# v2.net
KiCad netlist of a schematic drawn in Altium Designer
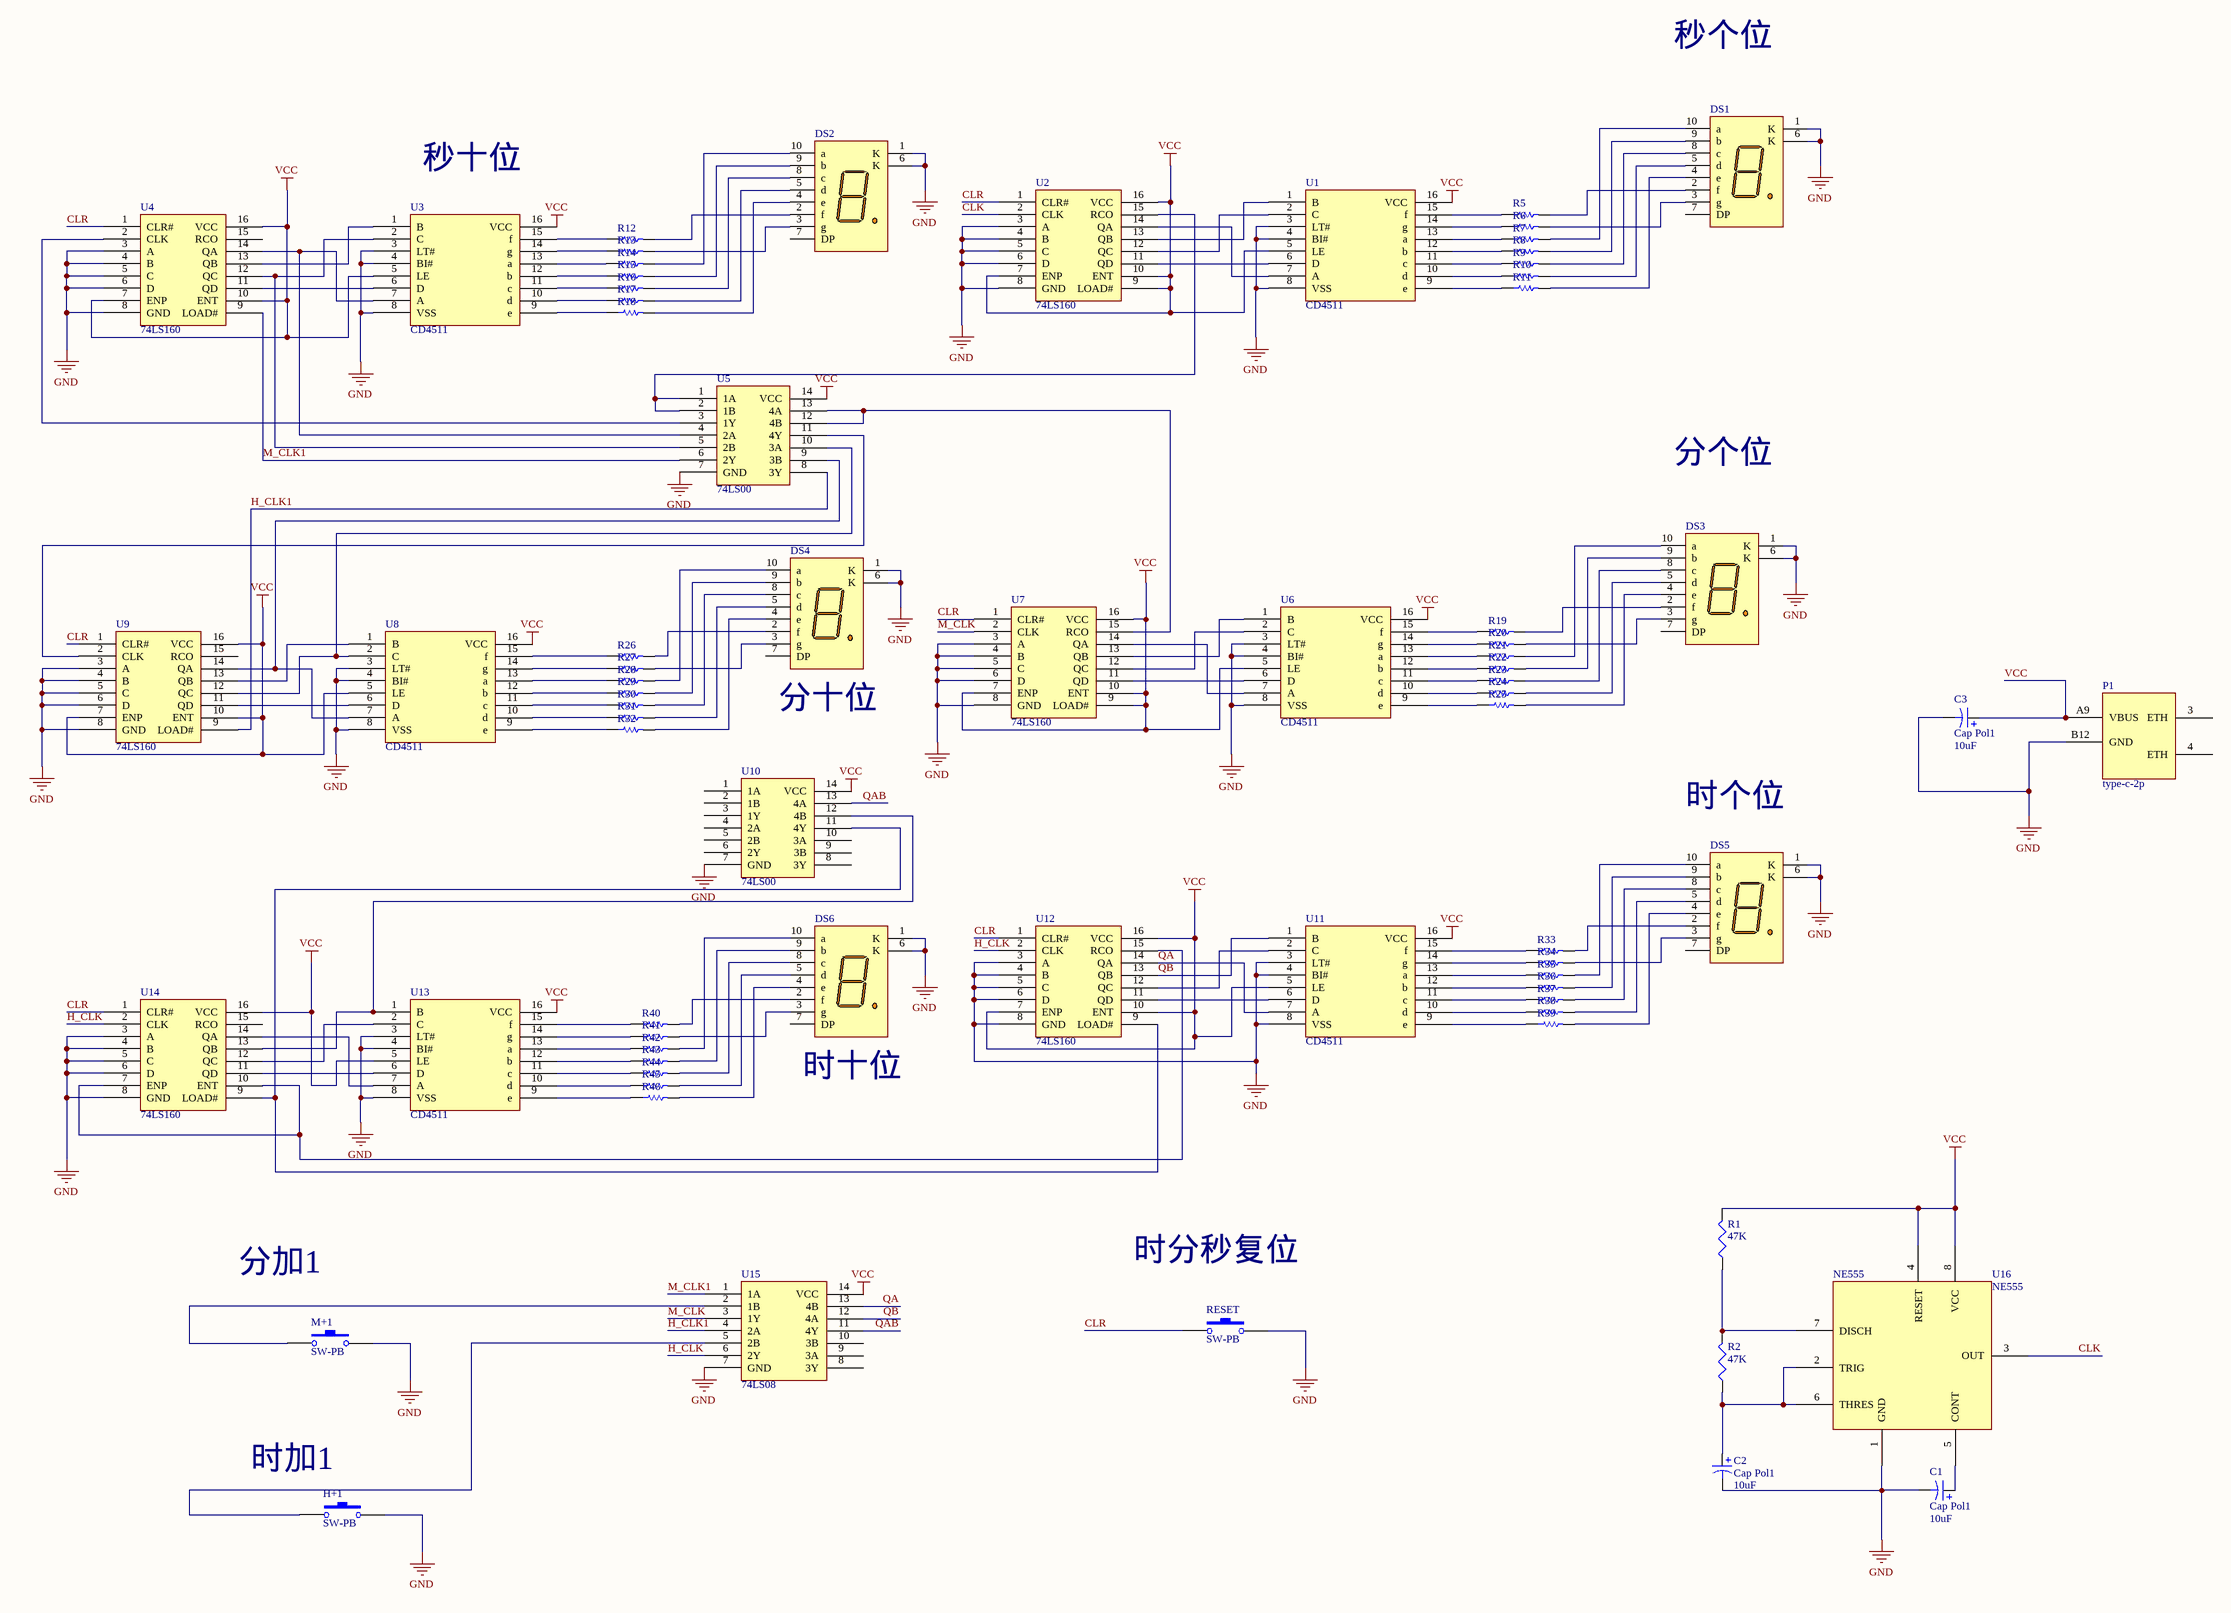
[diagram p0: 数字时钟v2.SchDoc]

(export (version "E")
  (design (tool "Eeschema 10.0.6"))
  (components
    (comp (ref "C1")
      (value "Cap Pol1")
      (footprint "RB7.6-15")
      (description "Polarized Capacitor (Radial)")
      (fields (field (name "ALTIUM_VALUE") "10uF") (field (name "PUBLISHER") "Altium Limited"))
      (libsource (lib "Miscellaneous Devices") (part "Cap Pol1"))
    )
    (comp (ref "C2")
      (value "Cap Pol1")
      (footprint "RB7.6-15")
      (description "Polarized Capacitor (Radial)")
      (fields (field (name "ALTIUM_VALUE") "10uF") (field (name "PUBLISHER") "Altium Limited"))
      (libsource (lib "Miscellaneous Devices") (part "Cap Pol1"))
    )
    (comp (ref "C3")
      (value "Cap Pol1")
      (footprint "RB7.6-15")
      (description "Polarized Capacitor (Radial)")
      (fields (field (name "ALTIUM_VALUE") "10uF") (field (name "PUBLISHER") "Altium Limited"))
      (libsource (lib "Miscellaneous Devices") (part "Cap Pol1"))
    )
    (comp (ref "DS1")
      (value "Dpy Amber-CC")
      (footprint "A")
      (description "7.62 mm Black Surface Orange 7-Segment Display: CC, RH DP")
      (fields (field (name "PUBLISHER") "Altium Limited"))
      (libsource (lib "Miscellaneous Devices") (part "Dpy Amber-CC"))
    )
    (comp (ref "DS2")
      (value "Dpy Amber-CC")
      (footprint "A")
      (description "7.62 mm Black Surface Orange 7-Segment Display: CC, RH DP")
      (fields (field (name "PUBLISHER") "Altium Limited"))
      (libsource (lib "Miscellaneous Devices") (part "Dpy Amber-CC"))
    )
    (comp (ref "DS3")
      (value "Dpy Amber-CC")
      (footprint "A")
      (description "7.62 mm Black Surface Orange 7-Segment Display: CC, RH DP")
      (fields (field (name "PUBLISHER") "Altium Limited"))
      (libsource (lib "Miscellaneous Devices") (part "Dpy Amber-CC"))
    )
    (comp (ref "DS4")
      (value "Dpy Amber-CC")
      (footprint "A")
      (description "7.62 mm Black Surface Orange 7-Segment Display: CC, RH DP")
      (fields (field (name "PUBLISHER") "Altium Limited"))
      (libsource (lib "Miscellaneous Devices") (part "Dpy Amber-CC"))
    )
    (comp (ref "DS5")
      (value "Dpy Amber-CC")
      (footprint "A")
      (description "7.62 mm Black Surface Orange 7-Segment Display: CC, RH DP")
      (fields (field (name "PUBLISHER") "Altium Limited"))
      (libsource (lib "Miscellaneous Devices") (part "Dpy Amber-CC"))
    )
    (comp (ref "DS6")
      (value "Dpy Amber-CC")
      (footprint "A")
      (description "7.62 mm Black Surface Orange 7-Segment Display: CC, RH DP")
      (fields (field (name "PUBLISHER") "Altium Limited"))
      (libsource (lib "Miscellaneous Devices") (part "Dpy Amber-CC"))
    )
    (comp (ref "H+1")
      (value "SW-PB")
      (footprint "按键")
      (description "Switch")
      (fields (field (name "PUBLISHER") "Altium Limited"))
      (libsource (lib "Miscellaneous Devices") (part "SW-PB"))
    )
    (comp (ref "M+1")
      (value "SW-PB")
      (footprint "按键")
      (description "Switch")
      (fields (field (name "PUBLISHER") "Altium Limited"))
      (libsource (lib "Miscellaneous Devices") (part "SW-PB"))
    )
    (comp (ref "P1")
      (value "type-c-2p")
      (footprint "type-c-2p")
      (libsource (lib "数字电路时钟") (part "type-c-2p"))
    )
    (comp (ref "R1")
      (value "47K")
      (footprint "AXIAL-0.3")
      (description "Resistor")
      (fields (field (name "Comment") "Res3") (field (name "PUBLISHER") "Altium Limited"))
      (libsource (lib "Miscellaneous Devices") (part "Res3"))
    )
    (comp (ref "R2")
      (value "47K")
      (footprint "AXIAL-0.3")
      (description "Resistor")
      (fields (field (name "Comment") "Res3") (field (name "PUBLISHER") "Altium Limited"))
      (libsource (lib "Miscellaneous Devices") (part "Res3"))
    )
    (comp (ref "R5")
      (value "Res1")
      (footprint "AXIAL-0.3")
      (description "Resistor")
      (fields (field (name "PUBLISHER") "Altium Limited"))
      (libsource (lib "Miscellaneous Devices") (part "Res1"))
    )
    (comp (ref "R6")
      (value "Res1")
      (footprint "AXIAL-0.3")
      (description "Resistor")
      (fields (field (name "PUBLISHER") "Altium Limited"))
      (libsource (lib "Miscellaneous Devices") (part "Res1"))
    )
    (comp (ref "R7")
      (value "Res1")
      (footprint "AXIAL-0.3")
      (description "Resistor")
      (fields (field (name "PUBLISHER") "Altium Limited"))
      (libsource (lib "Miscellaneous Devices") (part "Res1"))
    )
    (comp (ref "R8")
      (value "Res1")
      (footprint "AXIAL-0.3")
      (description "Resistor")
      (fields (field (name "PUBLISHER") "Altium Limited"))
      (libsource (lib "Miscellaneous Devices") (part "Res1"))
    )
    (comp (ref "R9")
      (value "Res1")
      (footprint "AXIAL-0.3")
      (description "Resistor")
      (fields (field (name "PUBLISHER") "Altium Limited"))
      (libsource (lib "Miscellaneous Devices") (part "Res1"))
    )
    (comp (ref "R10")
      (value "Res1")
      (footprint "AXIAL-0.3")
      (description "Resistor")
      (fields (field (name "PUBLISHER") "Altium Limited"))
      (libsource (lib "Miscellaneous Devices") (part "Res1"))
    )
    (comp (ref "R11")
      (value "Res1")
      (footprint "AXIAL-0.3")
      (description "Resistor")
      (fields (field (name "PUBLISHER") "Altium Limited"))
      (libsource (lib "Miscellaneous Devices") (part "Res1"))
    )
    (comp (ref "R12")
      (value "Res1")
      (footprint "AXIAL-0.3")
      (description "Resistor")
      (fields (field (name "PUBLISHER") "Altium Limited"))
      (libsource (lib "Miscellaneous Devices") (part "Res1"))
    )
    (comp (ref "R13")
      (value "Res1")
      (footprint "AXIAL-0.3")
      (description "Resistor")
      (fields (field (name "PUBLISHER") "Altium Limited"))
      (libsource (lib "Miscellaneous Devices") (part "Res1"))
    )
    (comp (ref "R14")
      (value "Res1")
      (footprint "AXIAL-0.3")
      (description "Resistor")
      (fields (field (name "PUBLISHER") "Altium Limited"))
      (libsource (lib "Miscellaneous Devices") (part "Res1"))
    )
    (comp (ref "R15")
      (value "Res1")
      (footprint "AXIAL-0.3")
      (description "Resistor")
      (fields (field (name "PUBLISHER") "Altium Limited"))
      (libsource (lib "Miscellaneous Devices") (part "Res1"))
    )
    (comp (ref "R16")
      (value "Res1")
      (footprint "AXIAL-0.3")
      (description "Resistor")
      (fields (field (name "PUBLISHER") "Altium Limited"))
      (libsource (lib "Miscellaneous Devices") (part "Res1"))
    )
    (comp (ref "R17")
      (value "Res1")
      (footprint "AXIAL-0.3")
      (description "Resistor")
      (fields (field (name "PUBLISHER") "Altium Limited"))
      (libsource (lib "Miscellaneous Devices") (part "Res1"))
    )
    (comp (ref "R18")
      (value "Res1")
      (footprint "AXIAL-0.3")
      (description "Resistor")
      (fields (field (name "PUBLISHER") "Altium Limited"))
      (libsource (lib "Miscellaneous Devices") (part "Res1"))
    )
    (comp (ref "R19")
      (value "Res1")
      (footprint "AXIAL-0.3")
      (description "Resistor")
      (fields (field (name "PUBLISHER") "Altium Limited"))
      (libsource (lib "Miscellaneous Devices") (part "Res1"))
    )
    (comp (ref "R20")
      (value "Res1")
      (footprint "AXIAL-0.3")
      (description "Resistor")
      (fields (field (name "PUBLISHER") "Altium Limited"))
      (libsource (lib "Miscellaneous Devices") (part "Res1"))
    )
    (comp (ref "R21")
      (value "Res1")
      (footprint "AXIAL-0.3")
      (description "Resistor")
      (fields (field (name "PUBLISHER") "Altium Limited"))
      (libsource (lib "Miscellaneous Devices") (part "Res1"))
    )
    (comp (ref "R22")
      (value "Res1")
      (footprint "AXIAL-0.3")
      (description "Resistor")
      (fields (field (name "PUBLISHER") "Altium Limited"))
      (libsource (lib "Miscellaneous Devices") (part "Res1"))
    )
    (comp (ref "R23")
      (value "Res1")
      (footprint "AXIAL-0.3")
      (description "Resistor")
      (fields (field (name "PUBLISHER") "Altium Limited"))
      (libsource (lib "Miscellaneous Devices") (part "Res1"))
    )
    (comp (ref "R24")
      (value "Res1")
      (footprint "AXIAL-0.3")
      (description "Resistor")
      (fields (field (name "PUBLISHER") "Altium Limited"))
      (libsource (lib "Miscellaneous Devices") (part "Res1"))
    )
    (comp (ref "R25")
      (value "Res1")
      (footprint "AXIAL-0.3")
      (description "Resistor")
      (fields (field (name "PUBLISHER") "Altium Limited"))
      (libsource (lib "Miscellaneous Devices") (part "Res1"))
    )
    (comp (ref "R26")
      (value "Res1")
      (footprint "AXIAL-0.3")
      (description "Resistor")
      (fields (field (name "PUBLISHER") "Altium Limited"))
      (libsource (lib "Miscellaneous Devices") (part "Res1"))
    )
    (comp (ref "R27")
      (value "Res1")
      (footprint "AXIAL-0.3")
      (description "Resistor")
      (fields (field (name "PUBLISHER") "Altium Limited"))
      (libsource (lib "Miscellaneous Devices") (part "Res1"))
    )
    (comp (ref "R28")
      (value "Res1")
      (footprint "AXIAL-0.3")
      (description "Resistor")
      (fields (field (name "PUBLISHER") "Altium Limited"))
      (libsource (lib "Miscellaneous Devices") (part "Res1"))
    )
    (comp (ref "R29")
      (value "Res1")
      (footprint "AXIAL-0.3")
      (description "Resistor")
      (fields (field (name "PUBLISHER") "Altium Limited"))
      (libsource (lib "Miscellaneous Devices") (part "Res1"))
    )
    (comp (ref "R30")
      (value "Res1")
      (footprint "AXIAL-0.3")
      (description "Resistor")
      (fields (field (name "PUBLISHER") "Altium Limited"))
      (libsource (lib "Miscellaneous Devices") (part "Res1"))
    )
    (comp (ref "R31")
      (value "Res1")
      (footprint "AXIAL-0.3")
      (description "Resistor")
      (fields (field (name "PUBLISHER") "Altium Limited"))
      (libsource (lib "Miscellaneous Devices") (part "Res1"))
    )
    (comp (ref "R32")
      (value "Res1")
      (footprint "AXIAL-0.3")
      (description "Resistor")
      (fields (field (name "PUBLISHER") "Altium Limited"))
      (libsource (lib "Miscellaneous Devices") (part "Res1"))
    )
    (comp (ref "R33")
      (value "Res1")
      (footprint "AXIAL-0.3")
      (description "Resistor")
      (fields (field (name "PUBLISHER") "Altium Limited"))
      (libsource (lib "Miscellaneous Devices") (part "Res1"))
    )
    (comp (ref "R34")
      (value "Res1")
      (footprint "AXIAL-0.3")
      (description "Resistor")
      (fields (field (name "PUBLISHER") "Altium Limited"))
      (libsource (lib "Miscellaneous Devices") (part "Res1"))
    )
    (comp (ref "R35")
      (value "Res1")
      (footprint "AXIAL-0.3")
      (description "Resistor")
      (fields (field (name "PUBLISHER") "Altium Limited"))
      (libsource (lib "Miscellaneous Devices") (part "Res1"))
    )
    (comp (ref "R36")
      (value "Res1")
      (footprint "AXIAL-0.3")
      (description "Resistor")
      (fields (field (name "PUBLISHER") "Altium Limited"))
      (libsource (lib "Miscellaneous Devices") (part "Res1"))
    )
    (comp (ref "R37")
      (value "Res1")
      (footprint "AXIAL-0.3")
      (description "Resistor")
      (fields (field (name "PUBLISHER") "Altium Limited"))
      (libsource (lib "Miscellaneous Devices") (part "Res1"))
    )
    (comp (ref "R38")
      (value "Res1")
      (footprint "AXIAL-0.3")
      (description "Resistor")
      (fields (field (name "PUBLISHER") "Altium Limited"))
      (libsource (lib "Miscellaneous Devices") (part "Res1"))
    )
    (comp (ref "R39")
      (value "Res1")
      (footprint "AXIAL-0.3")
      (description "Resistor")
      (fields (field (name "PUBLISHER") "Altium Limited"))
      (libsource (lib "Miscellaneous Devices") (part "Res1"))
    )
    (comp (ref "R40")
      (value "Res1")
      (footprint "AXIAL-0.3")
      (description "Resistor")
      (fields (field (name "PUBLISHER") "Altium Limited"))
      (libsource (lib "Miscellaneous Devices") (part "Res1"))
    )
    (comp (ref "R41")
      (value "Res1")
      (footprint "AXIAL-0.3")
      (description "Resistor")
      (fields (field (name "PUBLISHER") "Altium Limited"))
      (libsource (lib "Miscellaneous Devices") (part "Res1"))
    )
    (comp (ref "R42")
      (value "Res1")
      (footprint "AXIAL-0.3")
      (description "Resistor")
      (fields (field (name "PUBLISHER") "Altium Limited"))
      (libsource (lib "Miscellaneous Devices") (part "Res1"))
    )
    (comp (ref "R43")
      (value "Res1")
      (footprint "AXIAL-0.3")
      (description "Resistor")
      (fields (field (name "PUBLISHER") "Altium Limited"))
      (libsource (lib "Miscellaneous Devices") (part "Res1"))
    )
    (comp (ref "R44")
      (value "Res1")
      (footprint "AXIAL-0.3")
      (description "Resistor")
      (fields (field (name "PUBLISHER") "Altium Limited"))
      (libsource (lib "Miscellaneous Devices") (part "Res1"))
    )
    (comp (ref "R45")
      (value "Res1")
      (footprint "AXIAL-0.3")
      (description "Resistor")
      (fields (field (name "PUBLISHER") "Altium Limited"))
      (libsource (lib "Miscellaneous Devices") (part "Res1"))
    )
    (comp (ref "R46")
      (value "Res1")
      (footprint "AXIAL-0.3")
      (description "Resistor")
      (fields (field (name "PUBLISHER") "Altium Limited"))
      (libsource (lib "Miscellaneous Devices") (part "Res1"))
    )
    (comp (ref "RESET")
      (value "SW-PB")
      (footprint "按键")
      (description "Switch")
      (fields (field (name "PUBLISHER") "Altium Limited"))
      (libsource (lib "Miscellaneous Devices") (part "SW-PB"))
    )
    (comp (ref "U1") (value "CD4511") (footprint "CD4511BM/TR") (libsource (lib "数字电路时钟") (part "CD4511")))
    (comp (ref "U2") (value "74LS160") (footprint "DIP-16") (libsource (lib "数字电路时钟") (part "74LS160")))
    (comp (ref "U3") (value "CD4511") (footprint "CD4511BM/TR") (libsource (lib "数字电路时钟") (part "CD4511")))
    (comp (ref "U4") (value "74LS160") (footprint "DIP-16") (libsource (lib "数字电路时钟") (part "74LS160")))
    (comp (ref "U5") (value "74LS00") (footprint "DIP-14") (libsource (lib "数字电路时钟") (part "74LS00")))
    (comp (ref "U6") (value "CD4511") (footprint "CD4511BM/TR") (libsource (lib "数字电路时钟") (part "CD4511")))
    (comp (ref "U7") (value "74LS160") (footprint "DIP-16") (libsource (lib "数字电路时钟") (part "74LS160")))
    (comp (ref "U8") (value "CD4511") (footprint "CD4511BM/TR") (libsource (lib "数字电路时钟") (part "CD4511")))
    (comp (ref "U9") (value "74LS160") (footprint "DIP-16") (libsource (lib "数字电路时钟") (part "74LS160")))
    (comp (ref "U10") (value "74LS00") (footprint "DIP-14") (libsource (lib "数字电路时钟") (part "74LS00")))
    (comp (ref "U11") (value "CD4511") (footprint "CD4511BM/TR") (libsource (lib "数字电路时钟") (part "CD4511")))
    (comp (ref "U12") (value "74LS160") (footprint "DIP-16") (libsource (lib "数字电路时钟") (part "74LS160")))
    (comp (ref "U13") (value "CD4511") (footprint "CD4511BM/TR") (libsource (lib "数字电路时钟") (part "CD4511")))
    (comp (ref "U14") (value "74LS160") (footprint "DIP-16") (libsource (lib "数字电路时钟") (part "74LS160")))
    (comp (ref "U15") (value "74LS08") (footprint "DIP-14") (libsource (lib "数字电路时钟") (part "74LS08")))
    (comp (ref "U16") (value "NE555") (footprint "DIP-8") (libsource (lib "数字电路时钟") (part "NE555")))
  )
  (nets
    (net (code "1") (name "/CLK") (class "Default")
      (node (ref "U16") (pin "3") (pinfunction "OUT_3") (pintype "passive"))
      (node (ref "U2") (pin "2") (pinfunction "CLK_2") (pintype "passive"))
    )
    (net (code "2") (name "/CLR") (class "Default")
      (node (ref "RESET") (pin "1") (pinfunction "1_1") (pintype "passive"))
      (node (ref "U12") (pin "1") (pinfunction "CLR#_1") (pintype "passive"))
      (node (ref "U14") (pin "1") (pinfunction "CLR#_1") (pintype "passive"))
      (node (ref "U2") (pin "1") (pinfunction "CLR#_1") (pintype "passive"))
      (node (ref "U4") (pin "1") (pinfunction "CLR#_1") (pintype "passive"))
      (node (ref "U7") (pin "1") (pinfunction "CLR#_1") (pintype "passive"))
      (node (ref "U9") (pin "1") (pinfunction "CLR#_1") (pintype "passive"))
    )
    (net (code "3") (name "/H_CLK") (class "Default")
      (node (ref "U12") (pin "2") (pinfunction "CLK_2") (pintype "passive"))
      (node (ref "U14") (pin "2") (pinfunction "CLK_2") (pintype "passive"))
      (node (ref "U15") (pin "6") (pinfunction "2Y_6") (pintype "passive"))
    )
    (net (code "4") (name "/H_CLK1") (class "Default")
      (node (ref "U15") (pin "4") (pinfunction "2A_4") (pintype "passive"))
      (node (ref "U5") (pin "8") (pinfunction "3Y_8") (pintype "passive"))
      (node (ref "U9") (pin "9") (pinfunction "LOAD#_9") (pintype "passive"))
    )
    (net (code "5") (name "/M_CLK") (class "Default")
      (node (ref "U15") (pin "3") (pinfunction "1Y_3") (pintype "passive"))
      (node (ref "U7") (pin "2") (pinfunction "CLK_2") (pintype "passive"))
    )
    (net (code "6") (name "/M_CLK1") (class "Default")
      (node (ref "U15") (pin "1") (pinfunction "1A_1") (pintype "passive"))
      (node (ref "U4") (pin "9") (pinfunction "LOAD#_9") (pintype "passive"))
      (node (ref "U5") (pin "6") (pinfunction "2Y_6") (pintype "passive"))
    )
    (net (code "7") (name "/QA") (class "Default")
      (node (ref "U11") (pin "7") (pinfunction "A_7") (pintype "passive"))
      (node (ref "U12") (pin "14") (pinfunction "QA_14") (pintype "passive"))
      (node (ref "U15") (pin "13") (pinfunction "4B_13") (pintype "passive"))
    )
    (net (code "8") (name "/QAB") (class "Default")
      (node (ref "U10") (pin "13") (pinfunction "4A_13") (pintype "passive"))
      (node (ref "U15") (pin "11") (pinfunction "4Y_11") (pintype "passive"))
    )
    (net (code "9") (name "/QB") (class "Default")
      (node (ref "U11") (pin "1") (pinfunction "B_1") (pintype "passive"))
      (node (ref "U12") (pin "13") (pinfunction "QB_13") (pintype "passive"))
      (node (ref "U15") (pin "12") (pinfunction "4A_12") (pintype "passive"))
    )
    (net (code "10") (name "GND") (class "Default")
      (node (ref "C1") (pin "2") (pinfunction "2_2") (pintype "passive"))
      (node (ref "C2") (pin "2") (pinfunction "2_2") (pintype "passive"))
      (node (ref "C3") (pin "2") (pinfunction "2_2") (pintype "passive"))
      (node (ref "DS1") (pin "1") (pinfunction "K_1") (pintype "passive"))
      (node (ref "DS1") (pin "6") (pinfunction "K_6") (pintype "passive"))
      (node (ref "DS2") (pin "1") (pinfunction "K_1") (pintype "passive"))
      (node (ref "DS2") (pin "6") (pinfunction "K_6") (pintype "passive"))
      (node (ref "DS3") (pin "1") (pinfunction "K_1") (pintype "passive"))
      (node (ref "DS3") (pin "6") (pinfunction "K_6") (pintype "passive"))
      (node (ref "DS4") (pin "1") (pinfunction "K_1") (pintype "passive"))
      (node (ref "DS4") (pin "6") (pinfunction "K_6") (pintype "passive"))
      (node (ref "DS5") (pin "1") (pinfunction "K_1") (pintype "passive"))
      (node (ref "DS5") (pin "6") (pinfunction "K_6") (pintype "passive"))
      (node (ref "DS6") (pin "1") (pinfunction "K_1") (pintype "passive"))
      (node (ref "DS6") (pin "6") (pinfunction "K_6") (pintype "passive"))
      (node (ref "H+1") (pin "2") (pinfunction "2_2") (pintype "passive"))
      (node (ref "M+1") (pin "2") (pinfunction "2_2") (pintype "passive"))
      (node (ref "P1") (pin "B12") (pinfunction "GND_B12") (pintype "passive"))
      (node (ref "RESET") (pin "2") (pinfunction "2_2") (pintype "passive"))
      (node (ref "U1") (pin "3") (pinfunction "LT#_3") (pintype "passive"))
      (node (ref "U1") (pin "4") (pinfunction "BI#_4") (pintype "passive"))
      (node (ref "U1") (pin "8") (pinfunction "VSS_8") (pintype "passive"))
      (node (ref "U10") (pin "7") (pinfunction "GND_7") (pintype "passive"))
      (node (ref "U11") (pin "3") (pinfunction "LT#_3") (pintype "passive"))
      (node (ref "U11") (pin "4") (pinfunction "BI#_4") (pintype "passive"))
      (node (ref "U11") (pin "8") (pinfunction "VSS_8") (pintype "passive"))
      (node (ref "U12") (pin "3") (pinfunction "A_3") (pintype "passive"))
      (node (ref "U12") (pin "4") (pinfunction "B_4") (pintype "passive"))
      (node (ref "U12") (pin "5") (pinfunction "C_5") (pintype "passive"))
      (node (ref "U12") (pin "6") (pinfunction "D_6") (pintype "passive"))
      (node (ref "U12") (pin "8") (pinfunction "GND_8") (pintype "passive"))
      (node (ref "U13") (pin "3") (pinfunction "LT#_3") (pintype "passive"))
      (node (ref "U13") (pin "4") (pinfunction "BI#_4") (pintype "passive"))
      (node (ref "U13") (pin "8") (pinfunction "VSS_8") (pintype "passive"))
      (node (ref "U14") (pin "3") (pinfunction "A_3") (pintype "passive"))
      (node (ref "U14") (pin "4") (pinfunction "B_4") (pintype "passive"))
      (node (ref "U14") (pin "5") (pinfunction "C_5") (pintype "passive"))
      (node (ref "U14") (pin "6") (pinfunction "D_6") (pintype "passive"))
      (node (ref "U14") (pin "8") (pinfunction "GND_8") (pintype "passive"))
      (node (ref "U15") (pin "7") (pinfunction "GND_7") (pintype "passive"))
      (node (ref "U16") (pin "1") (pinfunction "GND_1") (pintype "passive"))
      (node (ref "U2") (pin "3") (pinfunction "A_3") (pintype "passive"))
      (node (ref "U2") (pin "4") (pinfunction "B_4") (pintype "passive"))
      (node (ref "U2") (pin "5") (pinfunction "C_5") (pintype "passive"))
      (node (ref "U2") (pin "6") (pinfunction "D_6") (pintype "passive"))
      (node (ref "U2") (pin "8") (pinfunction "GND_8") (pintype "passive"))
      (node (ref "U3") (pin "3") (pinfunction "LT#_3") (pintype "passive"))
      (node (ref "U3") (pin "4") (pinfunction "BI#_4") (pintype "passive"))
      (node (ref "U3") (pin "8") (pinfunction "VSS_8") (pintype "passive"))
      (node (ref "U4") (pin "3") (pinfunction "A_3") (pintype "passive"))
      (node (ref "U4") (pin "4") (pinfunction "B_4") (pintype "passive"))
      (node (ref "U4") (pin "5") (pinfunction "C_5") (pintype "passive"))
      (node (ref "U4") (pin "6") (pinfunction "D_6") (pintype "passive"))
      (node (ref "U4") (pin "8") (pinfunction "GND_8") (pintype "passive"))
      (node (ref "U5") (pin "7") (pinfunction "GND_7") (pintype "passive"))
      (node (ref "U6") (pin "3") (pinfunction "LT#_3") (pintype "passive"))
      (node (ref "U6") (pin "4") (pinfunction "BI#_4") (pintype "passive"))
      (node (ref "U6") (pin "8") (pinfunction "VSS_8") (pintype "passive"))
      (node (ref "U7") (pin "3") (pinfunction "A_3") (pintype "passive"))
      (node (ref "U7") (pin "4") (pinfunction "B_4") (pintype "passive"))
      (node (ref "U7") (pin "5") (pinfunction "C_5") (pintype "passive"))
      (node (ref "U7") (pin "6") (pinfunction "D_6") (pintype "passive"))
      (node (ref "U7") (pin "8") (pinfunction "GND_8") (pintype "passive"))
      (node (ref "U8") (pin "3") (pinfunction "LT#_3") (pintype "passive"))
      (node (ref "U8") (pin "4") (pinfunction "BI#_4") (pintype "passive"))
      (node (ref "U8") (pin "8") (pinfunction "VSS_8") (pintype "passive"))
      (node (ref "U9") (pin "3") (pinfunction "A_3") (pintype "passive"))
      (node (ref "U9") (pin "4") (pinfunction "B_4") (pintype "passive"))
      (node (ref "U9") (pin "5") (pinfunction "C_5") (pintype "passive"))
      (node (ref "U9") (pin "6") (pinfunction "D_6") (pintype "passive"))
      (node (ref "U9") (pin "8") (pinfunction "GND_8") (pintype "passive"))
    )
    (net (code "11") (name "Net-(DS1-a)") (class "Default")
      (node (ref "DS1") (pin "10") (pinfunction "a_10") (pintype "passive"))
      (node (ref "R7") (pin "2") (pinfunction "2_2") (pintype "passive"))
    )
    (net (code "12") (name "Net-(DS1-b)") (class "Default")
      (node (ref "DS1") (pin "9") (pinfunction "b_9") (pintype "passive"))
      (node (ref "R8") (pin "2") (pinfunction "2_2") (pintype "passive"))
    )
    (net (code "13") (name "Net-(DS1-c)") (class "Default")
      (node (ref "DS1") (pin "8") (pinfunction "c_8") (pintype "passive"))
      (node (ref "R9") (pin "2") (pinfunction "2_2") (pintype "passive"))
    )
    (net (code "14") (name "Net-(DS1-d)") (class "Default")
      (node (ref "DS1") (pin "5") (pinfunction "d_5") (pintype "passive"))
      (node (ref "R10") (pin "2") (pinfunction "2_2") (pintype "passive"))
    )
    (net (code "15") (name "Net-(DS1-e)") (class "Default")
      (node (ref "DS1") (pin "4") (pinfunction "e_4") (pintype "passive"))
      (node (ref "R11") (pin "2") (pinfunction "2_2") (pintype "passive"))
    )
    (net (code "16") (name "Net-(DS1-f)") (class "Default")
      (node (ref "DS1") (pin "2") (pinfunction "f_2") (pintype "passive"))
      (node (ref "R5") (pin "2") (pinfunction "2_2") (pintype "passive"))
    )
    (net (code "17") (name "Net-(DS1-g)") (class "Default")
      (node (ref "DS1") (pin "3") (pinfunction "g_3") (pintype "passive"))
      (node (ref "R6") (pin "2") (pinfunction "2_2") (pintype "passive"))
    )
    (net (code "18") (name "Net-(DS2-a)") (class "Default")
      (node (ref "DS2") (pin "10") (pinfunction "a_10") (pintype "passive"))
      (node (ref "R14") (pin "2") (pinfunction "2_2") (pintype "passive"))
    )
    (net (code "19") (name "Net-(DS2-b)") (class "Default")
      (node (ref "DS2") (pin "9") (pinfunction "b_9") (pintype "passive"))
      (node (ref "R15") (pin "2") (pinfunction "2_2") (pintype "passive"))
    )
    (net (code "20") (name "Net-(DS2-c)") (class "Default")
      (node (ref "DS2") (pin "8") (pinfunction "c_8") (pintype "passive"))
      (node (ref "R16") (pin "2") (pinfunction "2_2") (pintype "passive"))
    )
    (net (code "21") (name "Net-(DS2-d)") (class "Default")
      (node (ref "DS2") (pin "5") (pinfunction "d_5") (pintype "passive"))
      (node (ref "R17") (pin "2") (pinfunction "2_2") (pintype "passive"))
    )
    (net (code "22") (name "Net-(DS2-e)") (class "Default")
      (node (ref "DS2") (pin "4") (pinfunction "e_4") (pintype "passive"))
      (node (ref "R18") (pin "2") (pinfunction "2_2") (pintype "passive"))
    )
    (net (code "23") (name "Net-(DS2-f)") (class "Default")
      (node (ref "DS2") (pin "2") (pinfunction "f_2") (pintype "passive"))
      (node (ref "R12") (pin "2") (pinfunction "2_2") (pintype "passive"))
    )
    (net (code "24") (name "Net-(DS2-g)") (class "Default")
      (node (ref "DS2") (pin "3") (pinfunction "g_3") (pintype "passive"))
      (node (ref "R13") (pin "2") (pinfunction "2_2") (pintype "passive"))
    )
    (net (code "25") (name "Net-(DS3-a)") (class "Default")
      (node (ref "DS3") (pin "10") (pinfunction "a_10") (pintype "passive"))
      (node (ref "R21") (pin "2") (pinfunction "2_2") (pintype "passive"))
    )
    (net (code "26") (name "Net-(DS3-b)") (class "Default")
      (node (ref "DS3") (pin "9") (pinfunction "b_9") (pintype "passive"))
      (node (ref "R22") (pin "2") (pinfunction "2_2") (pintype "passive"))
    )
    (net (code "27") (name "Net-(DS3-c)") (class "Default")
      (node (ref "DS3") (pin "8") (pinfunction "c_8") (pintype "passive"))
      (node (ref "R23") (pin "2") (pinfunction "2_2") (pintype "passive"))
    )
    (net (code "28") (name "Net-(DS3-d)") (class "Default")
      (node (ref "DS3") (pin "5") (pinfunction "d_5") (pintype "passive"))
      (node (ref "R24") (pin "2") (pinfunction "2_2") (pintype "passive"))
    )
    (net (code "29") (name "Net-(DS3-e)") (class "Default")
      (node (ref "DS3") (pin "4") (pinfunction "e_4") (pintype "passive"))
      (node (ref "R25") (pin "2") (pinfunction "2_2") (pintype "passive"))
    )
    (net (code "30") (name "Net-(DS3-f)") (class "Default")
      (node (ref "DS3") (pin "2") (pinfunction "f_2") (pintype "passive"))
      (node (ref "R19") (pin "2") (pinfunction "2_2") (pintype "passive"))
    )
    (net (code "31") (name "Net-(DS3-g)") (class "Default")
      (node (ref "DS3") (pin "3") (pinfunction "g_3") (pintype "passive"))
      (node (ref "R20") (pin "2") (pinfunction "2_2") (pintype "passive"))
    )
    (net (code "32") (name "Net-(DS4-a)") (class "Default")
      (node (ref "DS4") (pin "10") (pinfunction "a_10") (pintype "passive"))
      (node (ref "R28") (pin "2") (pinfunction "2_2") (pintype "passive"))
    )
    (net (code "33") (name "Net-(DS4-b)") (class "Default")
      (node (ref "DS4") (pin "9") (pinfunction "b_9") (pintype "passive"))
      (node (ref "R29") (pin "2") (pinfunction "2_2") (pintype "passive"))
    )
    (net (code "34") (name "Net-(DS4-c)") (class "Default")
      (node (ref "DS4") (pin "8") (pinfunction "c_8") (pintype "passive"))
      (node (ref "R30") (pin "2") (pinfunction "2_2") (pintype "passive"))
    )
    (net (code "35") (name "Net-(DS4-d)") (class "Default")
      (node (ref "DS4") (pin "5") (pinfunction "d_5") (pintype "passive"))
      (node (ref "R31") (pin "2") (pinfunction "2_2") (pintype "passive"))
    )
    (net (code "36") (name "Net-(DS4-e)") (class "Default")
      (node (ref "DS4") (pin "4") (pinfunction "e_4") (pintype "passive"))
      (node (ref "R32") (pin "2") (pinfunction "2_2") (pintype "passive"))
    )
    (net (code "37") (name "Net-(DS4-f)") (class "Default")
      (node (ref "DS4") (pin "2") (pinfunction "f_2") (pintype "passive"))
      (node (ref "R26") (pin "2") (pinfunction "2_2") (pintype "passive"))
    )
    (net (code "38") (name "Net-(DS4-g)") (class "Default")
      (node (ref "DS4") (pin "3") (pinfunction "g_3") (pintype "passive"))
      (node (ref "R27") (pin "2") (pinfunction "2_2") (pintype "passive"))
    )
    (net (code "39") (name "Net-(DS5-a)") (class "Default")
      (node (ref "DS5") (pin "10") (pinfunction "a_10") (pintype "passive"))
      (node (ref "R35") (pin "2") (pinfunction "2_2") (pintype "passive"))
    )
    (net (code "40") (name "Net-(DS5-b)") (class "Default")
      (node (ref "DS5") (pin "9") (pinfunction "b_9") (pintype "passive"))
      (node (ref "R36") (pin "2") (pinfunction "2_2") (pintype "passive"))
    )
    (net (code "41") (name "Net-(DS5-c)") (class "Default")
      (node (ref "DS5") (pin "8") (pinfunction "c_8") (pintype "passive"))
      (node (ref "R37") (pin "2") (pinfunction "2_2") (pintype "passive"))
    )
    (net (code "42") (name "Net-(DS5-d)") (class "Default")
      (node (ref "DS5") (pin "5") (pinfunction "d_5") (pintype "passive"))
      (node (ref "R38") (pin "2") (pinfunction "2_2") (pintype "passive"))
    )
    (net (code "43") (name "Net-(DS5-e)") (class "Default")
      (node (ref "DS5") (pin "4") (pinfunction "e_4") (pintype "passive"))
      (node (ref "R39") (pin "2") (pinfunction "2_2") (pintype "passive"))
    )
    (net (code "44") (name "Net-(DS5-f)") (class "Default")
      (node (ref "DS5") (pin "2") (pinfunction "f_2") (pintype "passive"))
      (node (ref "R33") (pin "2") (pinfunction "2_2") (pintype "passive"))
    )
    (net (code "45") (name "Net-(DS5-g)") (class "Default")
      (node (ref "DS5") (pin "3") (pinfunction "g_3") (pintype "passive"))
      (node (ref "R34") (pin "2") (pinfunction "2_2") (pintype "passive"))
    )
    (net (code "46") (name "Net-(DS6-a)") (class "Default")
      (node (ref "DS6") (pin "10") (pinfunction "a_10") (pintype "passive"))
      (node (ref "R42") (pin "2") (pinfunction "2_2") (pintype "passive"))
    )
    (net (code "47") (name "Net-(DS6-b)") (class "Default")
      (node (ref "DS6") (pin "9") (pinfunction "b_9") (pintype "passive"))
      (node (ref "R43") (pin "2") (pinfunction "2_2") (pintype "passive"))
    )
    (net (code "48") (name "Net-(DS6-c)") (class "Default")
      (node (ref "DS6") (pin "8") (pinfunction "c_8") (pintype "passive"))
      (node (ref "R44") (pin "2") (pinfunction "2_2") (pintype "passive"))
    )
    (net (code "49") (name "Net-(DS6-d)") (class "Default")
      (node (ref "DS6") (pin "5") (pinfunction "d_5") (pintype "passive"))
      (node (ref "R45") (pin "2") (pinfunction "2_2") (pintype "passive"))
    )
    (net (code "50") (name "Net-(DS6-e)") (class "Default")
      (node (ref "DS6") (pin "4") (pinfunction "e_4") (pintype "passive"))
      (node (ref "R46") (pin "2") (pinfunction "2_2") (pintype "passive"))
    )
    (net (code "51") (name "Net-(DS6-f)") (class "Default")
      (node (ref "DS6") (pin "2") (pinfunction "f_2") (pintype "passive"))
      (node (ref "R40") (pin "2") (pinfunction "2_2") (pintype "passive"))
    )
    (net (code "52") (name "Net-(DS6-g)") (class "Default")
      (node (ref "DS6") (pin "3") (pinfunction "g_3") (pintype "passive"))
      (node (ref "R41") (pin "2") (pinfunction "2_2") (pintype "passive"))
    )
    (net (code "53") (name "Net-(U1-A)") (class "Default")
      (node (ref "U1") (pin "7") (pinfunction "A_7") (pintype "passive"))
      (node (ref "U2") (pin "14") (pinfunction "QA_14") (pintype "passive"))
    )
    (net (code "54") (name "Net-(U1-B)") (class "Default")
      (node (ref "U1") (pin "1") (pinfunction "B_1") (pintype "passive"))
      (node (ref "U2") (pin "13") (pinfunction "QB_13") (pintype "passive"))
    )
    (net (code "55") (name "Net-(U1-C)") (class "Default")
      (node (ref "U1") (pin "2") (pinfunction "C_2") (pintype "passive"))
      (node (ref "U2") (pin "12") (pinfunction "QC_12") (pintype "passive"))
    )
    (net (code "56") (name "Net-(U1-D)") (class "Default")
      (node (ref "U1") (pin "6") (pinfunction "D_6") (pintype "passive"))
      (node (ref "U2") (pin "11") (pinfunction "QD_11") (pintype "passive"))
    )
    (net (code "57") (name "Net-(U1-a)") (class "Default")
      (node (ref "R7") (pin "1") (pinfunction "1_1") (pintype "passive"))
      (node (ref "U1") (pin "13") (pinfunction "a_13") (pintype "passive"))
    )
    (net (code "58") (name "Net-(U1-b)") (class "Default")
      (node (ref "R8") (pin "1") (pinfunction "1_1") (pintype "passive"))
      (node (ref "U1") (pin "12") (pinfunction "b_12") (pintype "passive"))
    )
    (net (code "59") (name "Net-(U1-c)") (class "Default")
      (node (ref "R9") (pin "1") (pinfunction "1_1") (pintype "passive"))
      (node (ref "U1") (pin "11") (pinfunction "c_11") (pintype "passive"))
    )
    (net (code "60") (name "Net-(U1-d)") (class "Default")
      (node (ref "R10") (pin "1") (pinfunction "1_1") (pintype "passive"))
      (node (ref "U1") (pin "10") (pinfunction "d_10") (pintype "passive"))
    )
    (net (code "61") (name "Net-(U1-e)") (class "Default")
      (node (ref "R11") (pin "1") (pinfunction "1_1") (pintype "passive"))
      (node (ref "U1") (pin "9") (pinfunction "e_9") (pintype "passive"))
    )
    (net (code "62") (name "Net-(U1-f)") (class "Default")
      (node (ref "R5") (pin "1") (pinfunction "1_1") (pintype "passive"))
      (node (ref "U1") (pin "15") (pinfunction "f_15") (pintype "passive"))
    )
    (net (code "63") (name "Net-(U1-g)") (class "Default")
      (node (ref "R6") (pin "1") (pinfunction "1_1") (pintype "passive"))
      (node (ref "U1") (pin "14") (pinfunction "g_14") (pintype "passive"))
    )
    (net (code "64") (name "Net-(U2-RCO)") (class "Default")
      (node (ref "U2") (pin "15") (pinfunction "RCO_15") (pintype "passive"))
      (node (ref "U5") (pin "1") (pinfunction "1A_1") (pintype "passive"))
      (node (ref "U5") (pin "2") (pinfunction "1B_2") (pintype "passive"))
    )
    (net (code "65") (name "Net-(U3-A)") (class "Default")
      (node (ref "U3") (pin "7") (pinfunction "A_7") (pintype "passive"))
      (node (ref "U4") (pin "14") (pinfunction "QA_14") (pintype "passive"))
      (node (ref "U5") (pin "4") (pinfunction "2A_4") (pintype "passive"))
    )
    (net (code "66") (name "Net-(U3-B)") (class "Default")
      (node (ref "U3") (pin "1") (pinfunction "B_1") (pintype "passive"))
      (node (ref "U4") (pin "13") (pinfunction "QB_13") (pintype "passive"))
    )
    (net (code "67") (name "Net-(U3-C)") (class "Default")
      (node (ref "U3") (pin "2") (pinfunction "C_2") (pintype "passive"))
      (node (ref "U4") (pin "12") (pinfunction "QC_12") (pintype "passive"))
      (node (ref "U5") (pin "5") (pinfunction "2B_5") (pintype "passive"))
    )
    (net (code "68") (name "Net-(U3-D)") (class "Default")
      (node (ref "U3") (pin "6") (pinfunction "D_6") (pintype "passive"))
      (node (ref "U4") (pin "11") (pinfunction "QD_11") (pintype "passive"))
    )
    (net (code "69") (name "Net-(U3-a)") (class "Default")
      (node (ref "R14") (pin "1") (pinfunction "1_1") (pintype "passive"))
      (node (ref "U3") (pin "13") (pinfunction "a_13") (pintype "passive"))
    )
    (net (code "70") (name "Net-(U3-b)") (class "Default")
      (node (ref "R15") (pin "1") (pinfunction "1_1") (pintype "passive"))
      (node (ref "U3") (pin "12") (pinfunction "b_12") (pintype "passive"))
    )
    (net (code "71") (name "Net-(U3-c)") (class "Default")
      (node (ref "R16") (pin "1") (pinfunction "1_1") (pintype "passive"))
      (node (ref "U3") (pin "11") (pinfunction "c_11") (pintype "passive"))
    )
    (net (code "72") (name "Net-(U3-d)") (class "Default")
      (node (ref "R17") (pin "1") (pinfunction "1_1") (pintype "passive"))
      (node (ref "U3") (pin "10") (pinfunction "d_10") (pintype "passive"))
    )
    (net (code "73") (name "Net-(U3-e)") (class "Default")
      (node (ref "R18") (pin "1") (pinfunction "1_1") (pintype "passive"))
      (node (ref "U3") (pin "9") (pinfunction "e_9") (pintype "passive"))
    )
    (net (code "74") (name "Net-(U3-f)") (class "Default")
      (node (ref "R12") (pin "1") (pinfunction "1_1") (pintype "passive"))
      (node (ref "U3") (pin "15") (pinfunction "f_15") (pintype "passive"))
    )
    (net (code "75") (name "Net-(U3-g)") (class "Default")
      (node (ref "R13") (pin "1") (pinfunction "1_1") (pintype "passive"))
      (node (ref "U3") (pin "14") (pinfunction "g_14") (pintype "passive"))
    )
    (net (code "76") (name "Net-(U4-CLK)") (class "Default")
      (node (ref "U4") (pin "2") (pinfunction "CLK_2") (pintype "passive"))
      (node (ref "U5") (pin "3") (pinfunction "1Y_3") (pintype "passive"))
    )
    (net (code "77") (name "Net-(U5-3A)") (class "Default")
      (node (ref "U5") (pin "10") (pinfunction "3A_10") (pintype "passive"))
      (node (ref "U8") (pin "2") (pinfunction "C_2") (pintype "passive"))
      (node (ref "U9") (pin "12") (pinfunction "QC_12") (pintype "passive"))
    )
    (net (code "78") (name "Net-(U5-3B)") (class "Default")
      (node (ref "U5") (pin "9") (pinfunction "3B_9") (pintype "passive"))
      (node (ref "U8") (pin "7") (pinfunction "A_7") (pintype "passive"))
      (node (ref "U9") (pin "14") (pinfunction "QA_14") (pintype "passive"))
    )
    (net (code "79") (name "Net-(U5-4A)") (class "Default")
      (node (ref "U5") (pin "12") (pinfunction "4B_12") (pintype "passive"))
      (node (ref "U5") (pin "13") (pinfunction "4A_13") (pintype "passive"))
      (node (ref "U7") (pin "15") (pinfunction "RCO_15") (pintype "passive"))
    )
    (net (code "80") (name "Net-(U5-4Y)") (class "Default")
      (node (ref "U5") (pin "11") (pinfunction "4Y_11") (pintype "passive"))
      (node (ref "U9") (pin "2") (pinfunction "CLK_2") (pintype "passive"))
    )
    (net (code "81") (name "Net-(U6-A)") (class "Default")
      (node (ref "U6") (pin "7") (pinfunction "A_7") (pintype "passive"))
      (node (ref "U7") (pin "14") (pinfunction "QA_14") (pintype "passive"))
    )
    (net (code "82") (name "Net-(U6-B)") (class "Default")
      (node (ref "U6") (pin "1") (pinfunction "B_1") (pintype "passive"))
      (node (ref "U7") (pin "13") (pinfunction "QB_13") (pintype "passive"))
    )
    (net (code "83") (name "Net-(U6-C)") (class "Default")
      (node (ref "U6") (pin "2") (pinfunction "C_2") (pintype "passive"))
      (node (ref "U7") (pin "12") (pinfunction "QC_12") (pintype "passive"))
    )
    (net (code "84") (name "Net-(U6-D)") (class "Default")
      (node (ref "U6") (pin "6") (pinfunction "D_6") (pintype "passive"))
      (node (ref "U7") (pin "11") (pinfunction "QD_11") (pintype "passive"))
    )
    (net (code "85") (name "Net-(U6-a)") (class "Default")
      (node (ref "R21") (pin "1") (pinfunction "1_1") (pintype "passive"))
      (node (ref "U6") (pin "13") (pinfunction "a_13") (pintype "passive"))
    )
    (net (code "86") (name "Net-(U6-b)") (class "Default")
      (node (ref "R22") (pin "1") (pinfunction "1_1") (pintype "passive"))
      (node (ref "U6") (pin "12") (pinfunction "b_12") (pintype "passive"))
    )
    (net (code "87") (name "Net-(U6-c)") (class "Default")
      (node (ref "R23") (pin "1") (pinfunction "1_1") (pintype "passive"))
      (node (ref "U6") (pin "11") (pinfunction "c_11") (pintype "passive"))
    )
    (net (code "88") (name "Net-(U6-d)") (class "Default")
      (node (ref "R24") (pin "1") (pinfunction "1_1") (pintype "passive"))
      (node (ref "U6") (pin "10") (pinfunction "d_10") (pintype "passive"))
    )
    (net (code "89") (name "Net-(U6-e)") (class "Default")
      (node (ref "R25") (pin "1") (pinfunction "1_1") (pintype "passive"))
      (node (ref "U6") (pin "9") (pinfunction "e_9") (pintype "passive"))
    )
    (net (code "90") (name "Net-(U6-f)") (class "Default")
      (node (ref "R19") (pin "1") (pinfunction "1_1") (pintype "passive"))
      (node (ref "U6") (pin "15") (pinfunction "f_15") (pintype "passive"))
    )
    (net (code "91") (name "Net-(U6-g)") (class "Default")
      (node (ref "R20") (pin "1") (pinfunction "1_1") (pintype "passive"))
      (node (ref "U6") (pin "14") (pinfunction "g_14") (pintype "passive"))
    )
    (net (code "92") (name "Net-(U8-B)") (class "Default")
      (node (ref "U8") (pin "1") (pinfunction "B_1") (pintype "passive"))
      (node (ref "U9") (pin "13") (pinfunction "QB_13") (pintype "passive"))
    )
    (net (code "93") (name "Net-(U8-D)") (class "Default")
      (node (ref "U8") (pin "6") (pinfunction "D_6") (pintype "passive"))
      (node (ref "U9") (pin "11") (pinfunction "QD_11") (pintype "passive"))
    )
    (net (code "94") (name "Net-(U8-a)") (class "Default")
      (node (ref "R28") (pin "1") (pinfunction "1_1") (pintype "passive"))
      (node (ref "U8") (pin "13") (pinfunction "a_13") (pintype "passive"))
    )
    (net (code "95") (name "Net-(U8-b)") (class "Default")
      (node (ref "R29") (pin "1") (pinfunction "1_1") (pintype "passive"))
      (node (ref "U8") (pin "12") (pinfunction "b_12") (pintype "passive"))
    )
    (net (code "96") (name "Net-(U8-c)") (class "Default")
      (node (ref "R30") (pin "1") (pinfunction "1_1") (pintype "passive"))
      (node (ref "U8") (pin "11") (pinfunction "c_11") (pintype "passive"))
    )
    (net (code "97") (name "Net-(U8-d)") (class "Default")
      (node (ref "R31") (pin "1") (pinfunction "1_1") (pintype "passive"))
      (node (ref "U8") (pin "10") (pinfunction "d_10") (pintype "passive"))
    )
    (net (code "98") (name "Net-(U8-e)") (class "Default")
      (node (ref "R32") (pin "1") (pinfunction "1_1") (pintype "passive"))
      (node (ref "U8") (pin "9") (pinfunction "e_9") (pintype "passive"))
    )
    (net (code "99") (name "Net-(U8-f)") (class "Default")
      (node (ref "R26") (pin "1") (pinfunction "1_1") (pintype "passive"))
      (node (ref "U8") (pin "15") (pinfunction "f_15") (pintype "passive"))
    )
    (net (code "100") (name "Net-(U8-g)") (class "Default")
      (node (ref "R27") (pin "1") (pinfunction "1_1") (pintype "passive"))
      (node (ref "U8") (pin "14") (pinfunction "g_14") (pintype "passive"))
    )
    (net (code "101") (name "Net-(U10-4B)") (class "Default")
      (node (ref "U10") (pin "12") (pinfunction "4B_12") (pintype "passive"))
      (node (ref "U13") (pin "1") (pinfunction "B_1") (pintype "passive"))
      (node (ref "U14") (pin "13") (pinfunction "QB_13") (pintype "passive"))
    )
    (net (code "102") (name "Net-(U10-4Y)") (class "Default")
      (node (ref "U10") (pin "11") (pinfunction "4Y_11") (pintype "passive"))
      (node (ref "U12") (pin "9") (pinfunction "LOAD#_9") (pintype "passive"))
      (node (ref "U14") (pin "9") (pinfunction "LOAD#_9") (pintype "passive"))
    )
    (net (code "103") (name "Net-(U11-C)") (class "Default")
      (node (ref "U11") (pin "2") (pinfunction "C_2") (pintype "passive"))
      (node (ref "U12") (pin "12") (pinfunction "QC_12") (pintype "passive"))
    )
    (net (code "104") (name "Net-(U11-D)") (class "Default")
      (node (ref "U11") (pin "6") (pinfunction "D_6") (pintype "passive"))
      (node (ref "U12") (pin "11") (pinfunction "QD_11") (pintype "passive"))
    )
    (net (code "105") (name "Net-(U11-a)") (class "Default")
      (node (ref "R35") (pin "1") (pinfunction "1_1") (pintype "passive"))
      (node (ref "U11") (pin "13") (pinfunction "a_13") (pintype "passive"))
    )
    (net (code "106") (name "Net-(U11-b)") (class "Default")
      (node (ref "R36") (pin "1") (pinfunction "1_1") (pintype "passive"))
      (node (ref "U11") (pin "12") (pinfunction "b_12") (pintype "passive"))
    )
    (net (code "107") (name "Net-(U11-c)") (class "Default")
      (node (ref "R37") (pin "1") (pinfunction "1_1") (pintype "passive"))
      (node (ref "U11") (pin "11") (pinfunction "c_11") (pintype "passive"))
    )
    (net (code "108") (name "Net-(U11-d)") (class "Default")
      (node (ref "R38") (pin "1") (pinfunction "1_1") (pintype "passive"))
      (node (ref "U11") (pin "10") (pinfunction "d_10") (pintype "passive"))
    )
    (net (code "109") (name "Net-(U11-e)") (class "Default")
      (node (ref "R39") (pin "1") (pinfunction "1_1") (pintype "passive"))
      (node (ref "U11") (pin "9") (pinfunction "e_9") (pintype "passive"))
    )
    (net (code "110") (name "Net-(U11-f)") (class "Default")
      (node (ref "R33") (pin "1") (pinfunction "1_1") (pintype "passive"))
      (node (ref "U11") (pin "15") (pinfunction "f_15") (pintype "passive"))
    )
    (net (code "111") (name "Net-(U11-g)") (class "Default")
      (node (ref "R34") (pin "1") (pinfunction "1_1") (pintype "passive"))
      (node (ref "U11") (pin "14") (pinfunction "g_14") (pintype "passive"))
    )
    (net (code "112") (name "Net-(U12-RCO)") (class "Default")
      (node (ref "U12") (pin "15") (pinfunction "RCO_15") (pintype "passive"))
      (node (ref "U14") (pin "10") (pinfunction "ENT_10") (pintype "passive"))
      (node (ref "U14") (pin "7") (pinfunction "ENP_7") (pintype "passive"))
    )
    (net (code "113") (name "Net-(U13-A)") (class "Default")
      (node (ref "U13") (pin "7") (pinfunction "A_7") (pintype "passive"))
      (node (ref "U14") (pin "14") (pinfunction "QA_14") (pintype "passive"))
    )
    (net (code "114") (name "Net-(U13-C)") (class "Default")
      (node (ref "U13") (pin "2") (pinfunction "C_2") (pintype "passive"))
      (node (ref "U14") (pin "12") (pinfunction "QC_12") (pintype "passive"))
    )
    (net (code "115") (name "Net-(U13-D)") (class "Default")
      (node (ref "U13") (pin "6") (pinfunction "D_6") (pintype "passive"))
      (node (ref "U14") (pin "11") (pinfunction "QD_11") (pintype "passive"))
    )
    (net (code "116") (name "Net-(U13-a)") (class "Default")
      (node (ref "R42") (pin "1") (pinfunction "1_1") (pintype "passive"))
      (node (ref "U13") (pin "13") (pinfunction "a_13") (pintype "passive"))
    )
    (net (code "117") (name "Net-(U13-b)") (class "Default")
      (node (ref "R43") (pin "1") (pinfunction "1_1") (pintype "passive"))
      (node (ref "U13") (pin "12") (pinfunction "b_12") (pintype "passive"))
    )
    (net (code "118") (name "Net-(U13-c)") (class "Default")
      (node (ref "R44") (pin "1") (pinfunction "1_1") (pintype "passive"))
      (node (ref "U13") (pin "11") (pinfunction "c_11") (pintype "passive"))
    )
    (net (code "119") (name "Net-(U13-d)") (class "Default")
      (node (ref "R45") (pin "1") (pinfunction "1_1") (pintype "passive"))
      (node (ref "U13") (pin "10") (pinfunction "d_10") (pintype "passive"))
    )
    (net (code "120") (name "Net-(U13-e)") (class "Default")
      (node (ref "R46") (pin "1") (pinfunction "1_1") (pintype "passive"))
      (node (ref "U13") (pin "9") (pinfunction "e_9") (pintype "passive"))
    )
    (net (code "121") (name "Net-(U13-f)") (class "Default")
      (node (ref "R40") (pin "1") (pinfunction "1_1") (pintype "passive"))
      (node (ref "U13") (pin "15") (pinfunction "f_15") (pintype "passive"))
    )
    (net (code "122") (name "Net-(U13-g)") (class "Default")
      (node (ref "R41") (pin "1") (pinfunction "1_1") (pintype "passive"))
      (node (ref "U13") (pin "14") (pinfunction "g_14") (pintype "passive"))
    )
    (net (code "123") (name "Net-(U15-1B)") (class "Default")
      (node (ref "M+1") (pin "1") (pinfunction "1_1") (pintype "passive"))
      (node (ref "U15") (pin "2") (pinfunction "1B_2") (pintype "passive"))
    )
    (net (code "124") (name "Net-(U15-2B)") (class "Default")
      (node (ref "H+1") (pin "1") (pinfunction "1_1") (pintype "passive"))
      (node (ref "U15") (pin "5") (pinfunction "2B_5") (pintype "passive"))
    )
    (net (code "125") (name "Net-(U16-CONT)") (class "Default")
      (node (ref "C1") (pin "1") (pinfunction "1_1") (pintype "passive"))
      (node (ref "U16") (pin "5") (pinfunction "CONT_5") (pintype "passive"))
    )
    (net (code "126") (name "Net-(U16-DISCH)") (class "Default")
      (node (ref "R1") (pin "1") (pinfunction "1_1") (pintype "passive"))
      (node (ref "R2") (pin "2") (pinfunction "2_2") (pintype "passive"))
      (node (ref "U16") (pin "7") (pinfunction "DISCH_7") (pintype "passive"))
    )
    (net (code "127") (name "Net-(U16-THRES)") (class "Default")
      (node (ref "C2") (pin "1") (pinfunction "1_1") (pintype "passive"))
      (node (ref "R2") (pin "1") (pinfunction "1_1") (pintype "passive"))
      (node (ref "U16") (pin "2") (pinfunction "TRIG_2") (pintype "passive"))
      (node (ref "U16") (pin "6") (pinfunction "THRES_6") (pintype "passive"))
    )
    (net (code "128") (name "VCC") (class "Default")
      (node (ref "C3") (pin "1") (pinfunction "1_1") (pintype "passive"))
      (node (ref "P1") (pin "A9") (pinfunction "VBUS_A9") (pintype "passive"))
      (node (ref "R1") (pin "2") (pinfunction "2_2") (pintype "passive"))
      (node (ref "U1") (pin "16") (pinfunction "VCC_16") (pintype "passive"))
      (node (ref "U1") (pin "5") (pinfunction "LE_5") (pintype "passive"))
      (node (ref "U10") (pin "14") (pinfunction "VCC_14") (pintype "passive"))
      (node (ref "U11") (pin "16") (pinfunction "VCC_16") (pintype "passive"))
      (node (ref "U11") (pin "5") (pinfunction "LE_5") (pintype "passive"))
      (node (ref "U12") (pin "10") (pinfunction "ENT_10") (pintype "passive"))
      (node (ref "U12") (pin "16") (pinfunction "VCC_16") (pintype "passive"))
      (node (ref "U12") (pin "7") (pinfunction "ENP_7") (pintype "passive"))
      (node (ref "U13") (pin "16") (pinfunction "VCC_16") (pintype "passive"))
      (node (ref "U13") (pin "5") (pinfunction "LE_5") (pintype "passive"))
      (node (ref "U14") (pin "16") (pinfunction "VCC_16") (pintype "passive"))
      (node (ref "U15") (pin "14") (pinfunction "VCC_14") (pintype "passive"))
      (node (ref "U16") (pin "4") (pinfunction "RESET_4") (pintype "passive"))
      (node (ref "U16") (pin "8") (pinfunction "VCC_8") (pintype "passive"))
      (node (ref "U2") (pin "10") (pinfunction "ENT_10") (pintype "passive"))
      (node (ref "U2") (pin "16") (pinfunction "VCC_16") (pintype "passive"))
      (node (ref "U2") (pin "7") (pinfunction "ENP_7") (pintype "passive"))
      (node (ref "U2") (pin "9") (pinfunction "LOAD#_9") (pintype "passive"))
      (node (ref "U3") (pin "16") (pinfunction "VCC_16") (pintype "passive"))
      (node (ref "U3") (pin "5") (pinfunction "LE_5") (pintype "passive"))
      (node (ref "U4") (pin "10") (pinfunction "ENT_10") (pintype "passive"))
      (node (ref "U4") (pin "16") (pinfunction "VCC_16") (pintype "passive"))
      (node (ref "U4") (pin "7") (pinfunction "ENP_7") (pintype "passive"))
      (node (ref "U5") (pin "14") (pinfunction "VCC_14") (pintype "passive"))
      (node (ref "U6") (pin "16") (pinfunction "VCC_16") (pintype "passive"))
      (node (ref "U6") (pin "5") (pinfunction "LE_5") (pintype "passive"))
      (node (ref "U7") (pin "10") (pinfunction "ENT_10") (pintype "passive"))
      (node (ref "U7") (pin "16") (pinfunction "VCC_16") (pintype "passive"))
      (node (ref "U7") (pin "7") (pinfunction "ENP_7") (pintype "passive"))
      (node (ref "U7") (pin "9") (pinfunction "LOAD#_9") (pintype "passive"))
      (node (ref "U8") (pin "16") (pinfunction "VCC_16") (pintype "passive"))
      (node (ref "U8") (pin "5") (pinfunction "LE_5") (pintype "passive"))
      (node (ref "U9") (pin "10") (pinfunction "ENT_10") (pintype "passive"))
      (node (ref "U9") (pin "16") (pinfunction "VCC_16") (pintype "passive"))
      (node (ref "U9") (pin "7") (pinfunction "ENP_7") (pintype "passive"))
    )
    (net (code "129") (name "unconnected-(DS1-DP-Pad7)") (class "Default")
      (node (ref "DS1") (pin "7") (pinfunction "DP_7") (pintype "passive"))
    )
    (net (code "130") (name "unconnected-(DS2-DP-Pad7)") (class "Default")
      (node (ref "DS2") (pin "7") (pinfunction "DP_7") (pintype "passive"))
    )
    (net (code "131") (name "unconnected-(DS3-DP-Pad7)") (class "Default")
      (node (ref "DS3") (pin "7") (pinfunction "DP_7") (pintype "passive"))
    )
    (net (code "132") (name "unconnected-(DS4-DP-Pad7)") (class "Default")
      (node (ref "DS4") (pin "7") (pinfunction "DP_7") (pintype "passive"))
    )
    (net (code "133") (name "unconnected-(DS5-DP-Pad7)") (class "Default")
      (node (ref "DS5") (pin "7") (pinfunction "DP_7") (pintype "passive"))
    )
    (net (code "134") (name "unconnected-(DS6-DP-Pad7)") (class "Default")
      (node (ref "DS6") (pin "7") (pinfunction "DP_7") (pintype "passive"))
    )
    (net (code "135") (name "unconnected-(P1-ETH-Pad3)") (class "Default")
      (node (ref "P1") (pin "3") (pinfunction "ETH_3") (pintype "passive"))
    )
    (net (code "136") (name "unconnected-(P1-ETH-Pad4)") (class "Default")
      (node (ref "P1") (pin "4") (pinfunction "ETH_4") (pintype "passive"))
    )
    (net (code "137") (name "unconnected-(U4-RCO-Pad15)") (class "Default")
      (node (ref "U4") (pin "15") (pinfunction "RCO_15") (pintype "passive"))
    )
    (net (code "138") (name "unconnected-(U9-RCO-Pad15)") (class "Default")
      (node (ref "U9") (pin "15") (pinfunction "RCO_15") (pintype "passive"))
    )
    (net (code "139") (name "unconnected-(U10-1A-Pad1)") (class "Default")
      (node (ref "U10") (pin "1") (pinfunction "1A_1") (pintype "passive"))
    )
    (net (code "140") (name "unconnected-(U10-1B-Pad2)") (class "Default")
      (node (ref "U10") (pin "2") (pinfunction "1B_2") (pintype "passive"))
    )
    (net (code "141") (name "unconnected-(U10-1Y-Pad3)") (class "Default")
      (node (ref "U10") (pin "3") (pinfunction "1Y_3") (pintype "passive"))
    )
    (net (code "142") (name "unconnected-(U10-2A-Pad4)") (class "Default")
      (node (ref "U10") (pin "4") (pinfunction "2A_4") (pintype "passive"))
    )
    (net (code "143") (name "unconnected-(U10-2B-Pad5)") (class "Default")
      (node (ref "U10") (pin "5") (pinfunction "2B_5") (pintype "passive"))
    )
    (net (code "144") (name "unconnected-(U10-2Y-Pad6)") (class "Default")
      (node (ref "U10") (pin "6") (pinfunction "2Y_6") (pintype "passive"))
    )
    (net (code "145") (name "unconnected-(U10-3A-Pad10)") (class "Default")
      (node (ref "U10") (pin "10") (pinfunction "3A_10") (pintype "passive"))
    )
    (net (code "146") (name "unconnected-(U10-3B-Pad9)") (class "Default")
      (node (ref "U10") (pin "9") (pinfunction "3B_9") (pintype "passive"))
    )
    (net (code "147") (name "unconnected-(U10-3Y-Pad8)") (class "Default")
      (node (ref "U10") (pin "8") (pinfunction "3Y_8") (pintype "passive"))
    )
    (net (code "148") (name "unconnected-(U14-RCO-Pad15)") (class "Default")
      (node (ref "U14") (pin "15") (pinfunction "RCO_15") (pintype "passive"))
    )
    (net (code "149") (name "unconnected-(U15-3A-Pad9)") (class "Default")
      (node (ref "U15") (pin "9") (pinfunction "3A_9") (pintype "passive"))
    )
    (net (code "150") (name "unconnected-(U15-3B-Pad10)") (class "Default")
      (node (ref "U15") (pin "10") (pinfunction "3B_10") (pintype "passive"))
    )
    (net (code "151") (name "unconnected-(U15-3Y-Pad8)") (class "Default")
      (node (ref "U15") (pin "8") (pinfunction "3Y_8") (pintype "passive"))
    )
  )
)
